# Sheet1.net
KiCad netlist of a schematic drawn in Altium Designer
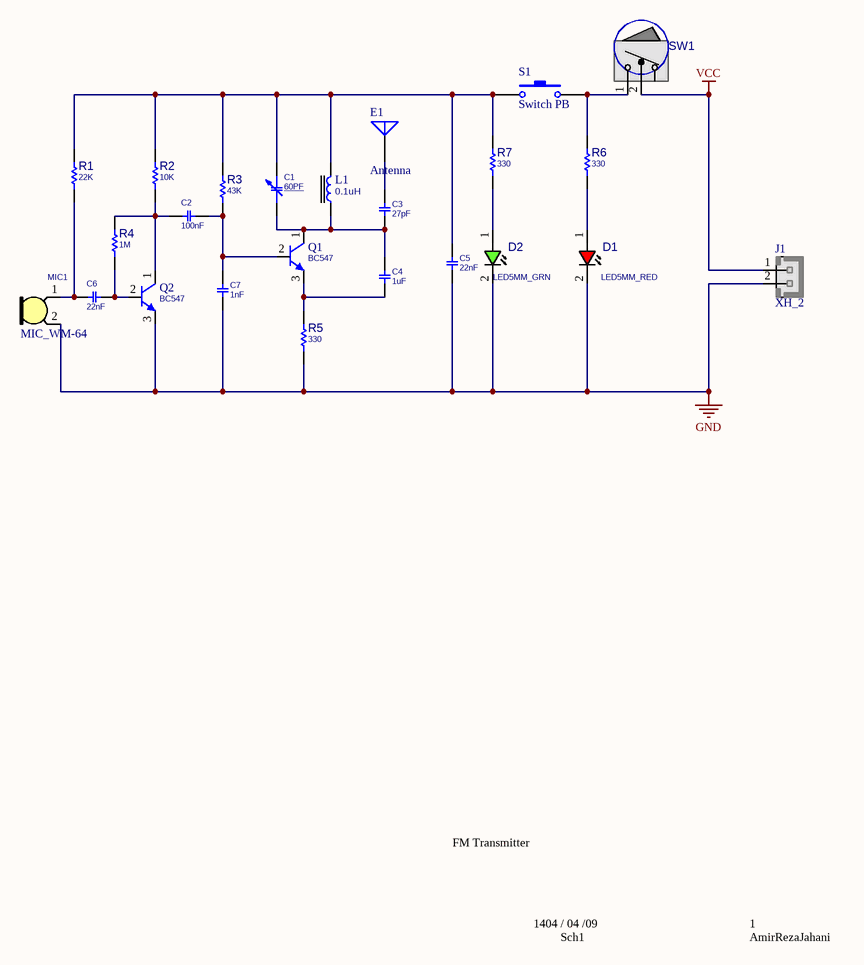
[diagram p0: Sheet1.SchDoc]

(export (version "E")
  (design (tool "Eeschema 10.0.6"))
  (components
    (comp (ref "C1")
      (value "60PF")
      (footprint "CTRM_6X6")
      (description "CAP, THD, TRIMMER")
      (fields (field (name "MANF_P#") "MANF_PART#") (field (name "MANF") "MANF"))
      (libsource (lib "passive_thd") (part "CAP_THD_TRIMMER"))
    )
    (comp (ref "C2")
      (value "100nF")
      (footprint "C_CER_D5")
      (description "CAP, THD, CER MULTI LAYER,")
      (fields (field (name "MANF_P#") "MANF_PART#") (field (name "MANF") "MANF"))
      (libsource (lib "passive_thd") (part "CAP_THD_CER"))
    )
    (comp (ref "C3")
      (value "27pF")
      (footprint "C_CER_D5")
      (description "CAP, THD, CER MULTI LAYER,")
      (fields (field (name "MANF_P#") "MANF_PART#") (field (name "MANF") "MANF"))
      (libsource (lib "passive_thd") (part "CAP_THD_CER"))
    )
    (comp (ref "C4")
      (value "1uF")
      (footprint "C_CER_D5")
      (description "CAP, THD, CER MULTI LAYER,")
      (fields (field (name "MANF_P#") "MANF_PART#") (field (name "MANF") "MANF"))
      (libsource (lib "passive_thd") (part "CAP_THD_CER"))
    )
    (comp (ref "C5")
      (value "22nF")
      (footprint "C_CER_D5")
      (description "CAP, THD, CER MULTI LAYER,")
      (fields (field (name "MANF_P#") "MANF_PART#") (field (name "MANF") "MANF"))
      (libsource (lib "passive_thd") (part "CAP_THD_CER"))
    )
    (comp (ref "C6")
      (value "22nF")
      (footprint "C_CER_D5")
      (description "CAP, THD, CER MULTI LAYER,")
      (fields (field (name "MANF_P#") "MANF_PART#") (field (name "MANF") "MANF"))
      (libsource (lib "passive_thd") (part "CAP_THD_CER"))
    )
    (comp (ref "C7")
      (value "1nF")
      (footprint "C_CER_D5")
      (description "CAP, THD, CER MULTI LAYER,")
      (fields (field (name "MANF_P#") "MANF_PART#") (field (name "MANF") "MANF"))
      (libsource (lib "passive_thd") (part "CAP_THD_CER"))
    )
    (comp (ref "D1")
      (value "LED5MM_RED")
      (footprint "LED5MM_RED")
      (description "LED, THD, 5MM, RED")
      (fields (field (name "MANF") "MANF") (field (name "MANF_P#") "MANF_PART#"))
      (libsource (lib "led(diode)") (part "LED_THD_5MM_RED"))
    )
    (comp (ref "D2")
      (value "LED5MM_GRN")
      (footprint "LED5MM_GRN")
      (description "LED, THD, 5MM, GREEN")
      (fields (field (name "MANF") "MANF") (field (name "MANF_P#") "MANF_PART#"))
      (libsource (lib "led(diode)") (part "LED_THD_5MM_GRN"))
    )
    (comp (ref "E1")
      (value "Antenna")
      (footprint "PIN1")
      (description "Generic Antenna")
      (fields (field (name "PUBLISHER") "Altium Limited"))
      (libsource (lib "Miscellaneous Devices") (part "Antenna"))
    )
    (comp (ref "J1")
      (value "XH_2")
      (footprint "XH_2")
      (description "PW10-x-M, JST-BxB-XH-A pitch: 2.5mm, 3A/250v")
      (fields (field (name "MANF") "JST") (field (name "MANF_P#") "B2B-XH-A"))
      (libsource (lib "conn_wire2board") (part "XH_2"))
    )
    (comp (ref "L1")
      (value "0.1uH")
      (footprint "LT_AX025")
      (description "INDUCTOR, THD")
      (libsource (lib "passive_thd") (part "IND_THD"))
    )
    (comp (ref "MIC1")
      (value "MIC_WM-64")
      (footprint "MIC_C6")
      (description "MICROPHONE OMNI 6X2.2MM W/CAP 2.2KOHM -44DB TH")
      (fields (field (name "MANF_P#") "WM-64PNT"))
      (libsource (lib "audio_mic_spk") (part "MIC_WM-64"))
    )
    (comp (ref "Q1")
      (value "BC547")
      (footprint "TO92_3")
      (description "BJT, NPN, 45v, 0.1A, THD, TO92")
      (fields (field (name "MANF") "FAIRCHILD"))
      (libsource (lib "transistor_bjt") (part "NPN_BC547_TO92"))
    )
    (comp (ref "Q2")
      (value "BC547")
      (footprint "TO92_3")
      (description "BJT, NPN, 45v, 0.1A, THD, TO92")
      (fields (field (name "MANF") "FAIRCHILD"))
      (libsource (lib "transistor_bjt") (part "NPN_BC547_TO92"))
    )
    (comp (ref "R1")
      (value "22K")
      (footprint "R025W_AX04")
      (description "RESISTOR, THD")
      (fields (field (name "MANF_P#") "RK73H1ETTP4701F") (field (name "MANF") "KOA SPEER"))
      (libsource (lib "passive_thd") (part "RES_THD"))
    )
    (comp (ref "R2")
      (value "10K")
      (footprint "R025W_AX04")
      (description "RESISTOR, THD")
      (fields (field (name "MANF_P#") "RK73H1ETTP4701F") (field (name "MANF") "KOA SPEER"))
      (libsource (lib "passive_thd") (part "RES_THD"))
    )
    (comp (ref "R3")
      (value "43K")
      (footprint "R025W_AX04")
      (description "RESISTOR, THD")
      (fields (field (name "MANF_P#") "RK73H1ETTP4701F") (field (name "MANF") "KOA SPEER"))
      (libsource (lib "passive_thd") (part "RES_THD"))
    )
    (comp (ref "R4")
      (value "1M")
      (footprint "R025W_AX04")
      (description "RESISTOR, THD")
      (fields (field (name "MANF_P#") "RK73H1ETTP4701F") (field (name "MANF") "KOA SPEER"))
      (libsource (lib "passive_thd") (part "RES_THD"))
    )
    (comp (ref "R5")
      (value "330")
      (footprint "R025W_AX04")
      (description "RESISTOR, THD")
      (fields (field (name "MANF_P#") "RK73H1ETTP4701F") (field (name "MANF") "KOA SPEER"))
      (libsource (lib "passive_thd") (part "RES_THD"))
    )
    (comp (ref "R6")
      (value "330")
      (footprint "R025W_AX04")
      (description "RESISTOR, THD")
      (fields (field (name "MANF_P#") "RK73H1ETTP4701F") (field (name "MANF") "KOA SPEER"))
      (libsource (lib "passive_thd") (part "RES_THD"))
    )
    (comp (ref "R7")
      (value "330")
      (footprint "R025W_AX04")
      (description "RESISTOR, THD")
      (fields (field (name "MANF_P#") "RK73H1ETTP4701F") (field (name "MANF") "KOA SPEER"))
      (libsource (lib "passive_thd") (part "RES_THD"))
    )
    (comp (ref "S1")
      (value "Switch PB")
      (footprint "Switch - Push to On")
      (description "Push Button Switch")
      (libsource (lib "My_Library") (part "Switch PB"))
    )
    (comp (ref "SW1")
      (value "ToggleSwitch")
      (footprint "SWRCK_SPST_S_15X10")
      (description "SWITCH, Rocker, SPST, THD, 15x10.5mm")
      (libsource (lib "switch_rocker") (part "SWROK_SPST_R_15X10"))
    )
  )
  (nets
    (net (code "1") (name "GND") (class "Default")
      (node (ref "C5") (pin "1") (pinfunction "1_1") (pintype "passive"))
      (node (ref "C7") (pin "1") (pinfunction "1_1") (pintype "passive"))
      (node (ref "D1") (pin "2") (pinfunction "CATHODE_2") (pintype "passive"))
      (node (ref "D2") (pin "2") (pinfunction "CATHODE_2") (pintype "passive"))
      (node (ref "J1") (pin "2") (pinfunction "2_2") (pintype "passive"))
      (node (ref "MIC1") (pin "2") (pinfunction "GND_2") (pintype "passive"))
      (node (ref "Q2") (pin "3") (pinfunction "E_3") (pintype "passive"))
      (node (ref "R5") (pin "1") (pinfunction "1_1") (pintype "passive"))
    )
    (net (code "2") (name "Net-(C1-Pad2)") (class "Default")
      (node (ref "C1") (pin "2") (pinfunction "2_2") (pintype "passive"))
      (node (ref "C5") (pin "2") (pinfunction "2_2") (pintype "passive"))
      (node (ref "L1") (pin "2") (pinfunction "2_2") (pintype "passive"))
      (node (ref "R1") (pin "2") (pinfunction "2_2") (pintype "passive"))
      (node (ref "R2") (pin "2") (pinfunction "2_2") (pintype "passive"))
      (node (ref "R3") (pin "2") (pinfunction "2_2") (pintype "passive"))
      (node (ref "R7") (pin "2") (pinfunction "2_2") (pintype "passive"))
      (node (ref "S1") (pin "1") (pinfunction "1_1") (pintype "passive"))
    )
    (net (code "3") (name "Net-(D1-ANODE)") (class "Default")
      (node (ref "D1") (pin "1") (pinfunction "ANODE_1") (pintype "passive"))
      (node (ref "R6") (pin "1") (pinfunction "1_1") (pintype "passive"))
    )
    (net (code "4") (name "Net-(D2-ANODE)") (class "Default")
      (node (ref "D2") (pin "1") (pinfunction "ANODE_1") (pintype "passive"))
      (node (ref "R7") (pin "1") (pinfunction "1_1") (pintype "passive"))
    )
    (net (code "5") (name "Net-(E1-A)") (class "Default")
      (node (ref "C3") (pin "2") (pinfunction "2_2") (pintype "passive"))
      (node (ref "E1") (pin "1") (pinfunction "A_1") (pintype "passive"))
    )
    (net (code "6") (name "Net-(MIC1-OUT)") (class "Default")
      (node (ref "C6") (pin "1") (pinfunction "1_1") (pintype "passive"))
      (node (ref "MIC1") (pin "1") (pinfunction "OUT_1") (pintype "passive"))
      (node (ref "R1") (pin "1") (pinfunction "1_1") (pintype "passive"))
    )
    (net (code "7") (name "Net-(Q1-B)") (class "Default")
      (node (ref "C2") (pin "2") (pinfunction "2_2") (pintype "passive"))
      (node (ref "C7") (pin "2") (pinfunction "2_2") (pintype "passive"))
      (node (ref "Q1") (pin "2") (pinfunction "B_2") (pintype "passive"))
      (node (ref "R3") (pin "1") (pinfunction "1_1") (pintype "passive"))
    )
    (net (code "8") (name "Net-(Q1-C)") (class "Default")
      (node (ref "C1") (pin "1") (pinfunction "1_1") (pintype "passive"))
      (node (ref "C3") (pin "1") (pinfunction "1_1") (pintype "passive"))
      (node (ref "C4") (pin "2") (pinfunction "2_2") (pintype "passive"))
      (node (ref "L1") (pin "1") (pinfunction "1_1") (pintype "passive"))
      (node (ref "Q1") (pin "1") (pinfunction "C_1") (pintype "passive"))
    )
    (net (code "9") (name "Net-(Q1-E)") (class "Default")
      (node (ref "C4") (pin "1") (pinfunction "1_1") (pintype "passive"))
      (node (ref "Q1") (pin "3") (pinfunction "E_3") (pintype "passive"))
      (node (ref "R5") (pin "2") (pinfunction "2_2") (pintype "passive"))
    )
    (net (code "10") (name "Net-(Q2-B)") (class "Default")
      (node (ref "C6") (pin "2") (pinfunction "2_2") (pintype "passive"))
      (node (ref "Q2") (pin "2") (pinfunction "B_2") (pintype "passive"))
      (node (ref "R4") (pin "1") (pinfunction "1_1") (pintype "passive"))
    )
    (net (code "11") (name "Net-(Q2-C)") (class "Default")
      (node (ref "C2") (pin "1") (pinfunction "1_1") (pintype "passive"))
      (node (ref "Q2") (pin "1") (pinfunction "C_1") (pintype "passive"))
      (node (ref "R2") (pin "1") (pinfunction "1_1") (pintype "passive"))
      (node (ref "R4") (pin "2") (pinfunction "2_2") (pintype "passive"))
    )
    (net (code "12") (name "Net-(SW1-T1)") (class "Default")
      (node (ref "R6") (pin "2") (pinfunction "2_2") (pintype "passive"))
      (node (ref "S1") (pin "2") (pinfunction "2_2") (pintype "passive"))
      (node (ref "SW1") (pin "1") (pinfunction "T1_1") (pintype "passive"))
    )
    (net (code "13") (name "VCC") (class "Default")
      (node (ref "J1") (pin "1") (pinfunction "1_1") (pintype "passive"))
      (node (ref "SW1") (pin "2") (pinfunction "COM_2") (pintype "passive"))
    )
  )
)
